# esp01-breadboard.net
KiCad netlist of a schematic drawn in EAGLE
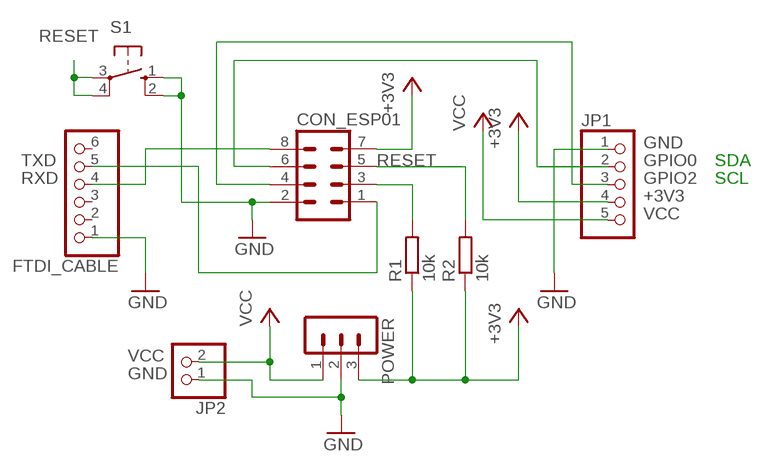
[diagram p0: schematic, sheet 1]

(export (version "E")
  (design (tool "Eeschema 10.0.6"))
  (components
    (comp (ref "CON_ESP01")
      (value "MA04-2")
      (footprint "eagle-import:MA04-2")
      (libsource (lib "eagle-import") (part "MA04-2"))
    )
    (comp (ref "FTDI_CABLE")
      (value "PINHD-1X6")
      (footprint "eagle-import:1X06")
      (libsource (lib "eagle-import") (part "PINHD-1X6"))
    )
    (comp (ref "JP1")
      (value "PINHD-1X5")
      (footprint "eagle-import:1X05")
      (libsource (lib "eagle-import") (part "PINHD-1X5"))
    )
    (comp (ref "JP2")
      (value "PINHD-1X2")
      (footprint "eagle-import:1X02")
      (libsource (lib "eagle-import") (part "PINHD-1X2"))
    )
    (comp (ref "POWER")
      (value "MA03-1")
      (footprint "eagle-import:MA03-1")
      (libsource (lib "eagle-import") (part "MA03-1"))
    )
    (comp (ref "R1")
      (value "10k")
      (footprint "eagle-import:0204_5")
      (libsource (lib "eagle-import") (part "R-EU_0204/5"))
    )
    (comp (ref "R2")
      (value "10k")
      (footprint "eagle-import:0204_5")
      (libsource (lib "eagle-import") (part "R-EU_0204/5"))
    )
    (comp (ref "S1")
      (value "10-XX")
      (footprint "eagle-import:B3F-10XX")
      (fields (field (name "MPN") "B3F-1000"))
      (libsource (lib "eagle-import") (part "10-XX"))
    )
  )
  (nets
    (net (code "1") (name "+3V3") (class "Default")
      (node (ref "CON_ESP01") (pin "7") (pinfunction "7_7") (pintype "passive"))
      (node (ref "JP1") (pin "4") (pinfunction "4_4") (pintype "passive"))
      (node (ref "POWER") (pin "3") (pinfunction "3_3") (pintype "passive"))
      (node (ref "R1") (pin "1") (pinfunction "1_1") (pintype "passive"))
      (node (ref "R2") (pin "1") (pinfunction "1_1") (pintype "passive"))
    )
    (net (code "2") (name "/GPIO0") (class "Default")
      (node (ref "CON_ESP01") (pin "6") (pinfunction "6_6") (pintype "passive"))
      (node (ref "JP1") (pin "2") (pinfunction "2_2") (pintype "passive"))
    )
    (net (code "3") (name "/GPIO2") (class "Default")
      (node (ref "CON_ESP01") (pin "4") (pinfunction "4_4") (pintype "passive"))
      (node (ref "JP1") (pin "3") (pinfunction "3_3") (pintype "passive"))
    )
    (net (code "4") (name "/RESET") (class "Default")
      (node (ref "CON_ESP01") (pin "5") (pinfunction "5_5") (pintype "passive"))
      (node (ref "R2") (pin "2") (pinfunction "2_2") (pintype "passive"))
      (node (ref "S1") (pin "3") (pinfunction "P_3") (pintype "passive"))
      (node (ref "S1") (pin "4") (pinfunction "P1_4") (pintype "passive"))
    )
    (net (code "5") (name "/RXD") (class "Default")
      (node (ref "CON_ESP01") (pin "8") (pinfunction "8_8") (pintype "passive"))
      (node (ref "FTDI_CABLE") (pin "4") (pinfunction "4_4") (pintype "passive"))
    )
    (net (code "6") (name "/TXD") (class "Default")
      (node (ref "CON_ESP01") (pin "1") (pinfunction "1_1") (pintype "passive"))
      (node (ref "FTDI_CABLE") (pin "5") (pinfunction "5_5") (pintype "passive"))
    )
    (net (code "7") (name "GND") (class "Default")
      (node (ref "CON_ESP01") (pin "2") (pinfunction "2_2") (pintype "passive"))
      (node (ref "FTDI_CABLE") (pin "1") (pinfunction "1_1") (pintype "passive"))
      (node (ref "JP1") (pin "1") (pinfunction "1_1") (pintype "passive"))
      (node (ref "JP2") (pin "1") (pinfunction "1_1") (pintype "passive"))
      (node (ref "POWER") (pin "2") (pinfunction "2_2") (pintype "passive"))
      (node (ref "S1") (pin "1") (pinfunction "S_1") (pintype "passive"))
      (node (ref "S1") (pin "2") (pinfunction "S1_2") (pintype "passive"))
    )
    (net (code "8") (name "Net-(CON_ESP01-Pad3)") (class "Default")
      (node (ref "CON_ESP01") (pin "3") (pinfunction "3_3") (pintype "passive"))
      (node (ref "R1") (pin "2") (pinfunction "2_2") (pintype "passive"))
    )
    (net (code "9") (name "VCC") (class "Default")
      (node (ref "JP1") (pin "5") (pinfunction "5_5") (pintype "passive"))
      (node (ref "JP2") (pin "2") (pinfunction "2_2") (pintype "passive"))
      (node (ref "POWER") (pin "1") (pinfunction "1_1") (pintype "passive"))
    )
    (net (code "10") (name "unconnected-(FTDI_CABLE-Pad2)") (class "Default")
      (node (ref "FTDI_CABLE") (pin "2") (pinfunction "2_2") (pintype "passive"))
    )
    (net (code "11") (name "unconnected-(FTDI_CABLE-Pad3)") (class "Default")
      (node (ref "FTDI_CABLE") (pin "3") (pinfunction "3_3") (pintype "passive"))
    )
    (net (code "12") (name "unconnected-(FTDI_CABLE-Pad6)") (class "Default")
      (node (ref "FTDI_CABLE") (pin "6") (pinfunction "6_6") (pintype "passive"))
    )
  )
)
